# diff_probe.net
KiCad netlist of a schematic drawn in EAGLE
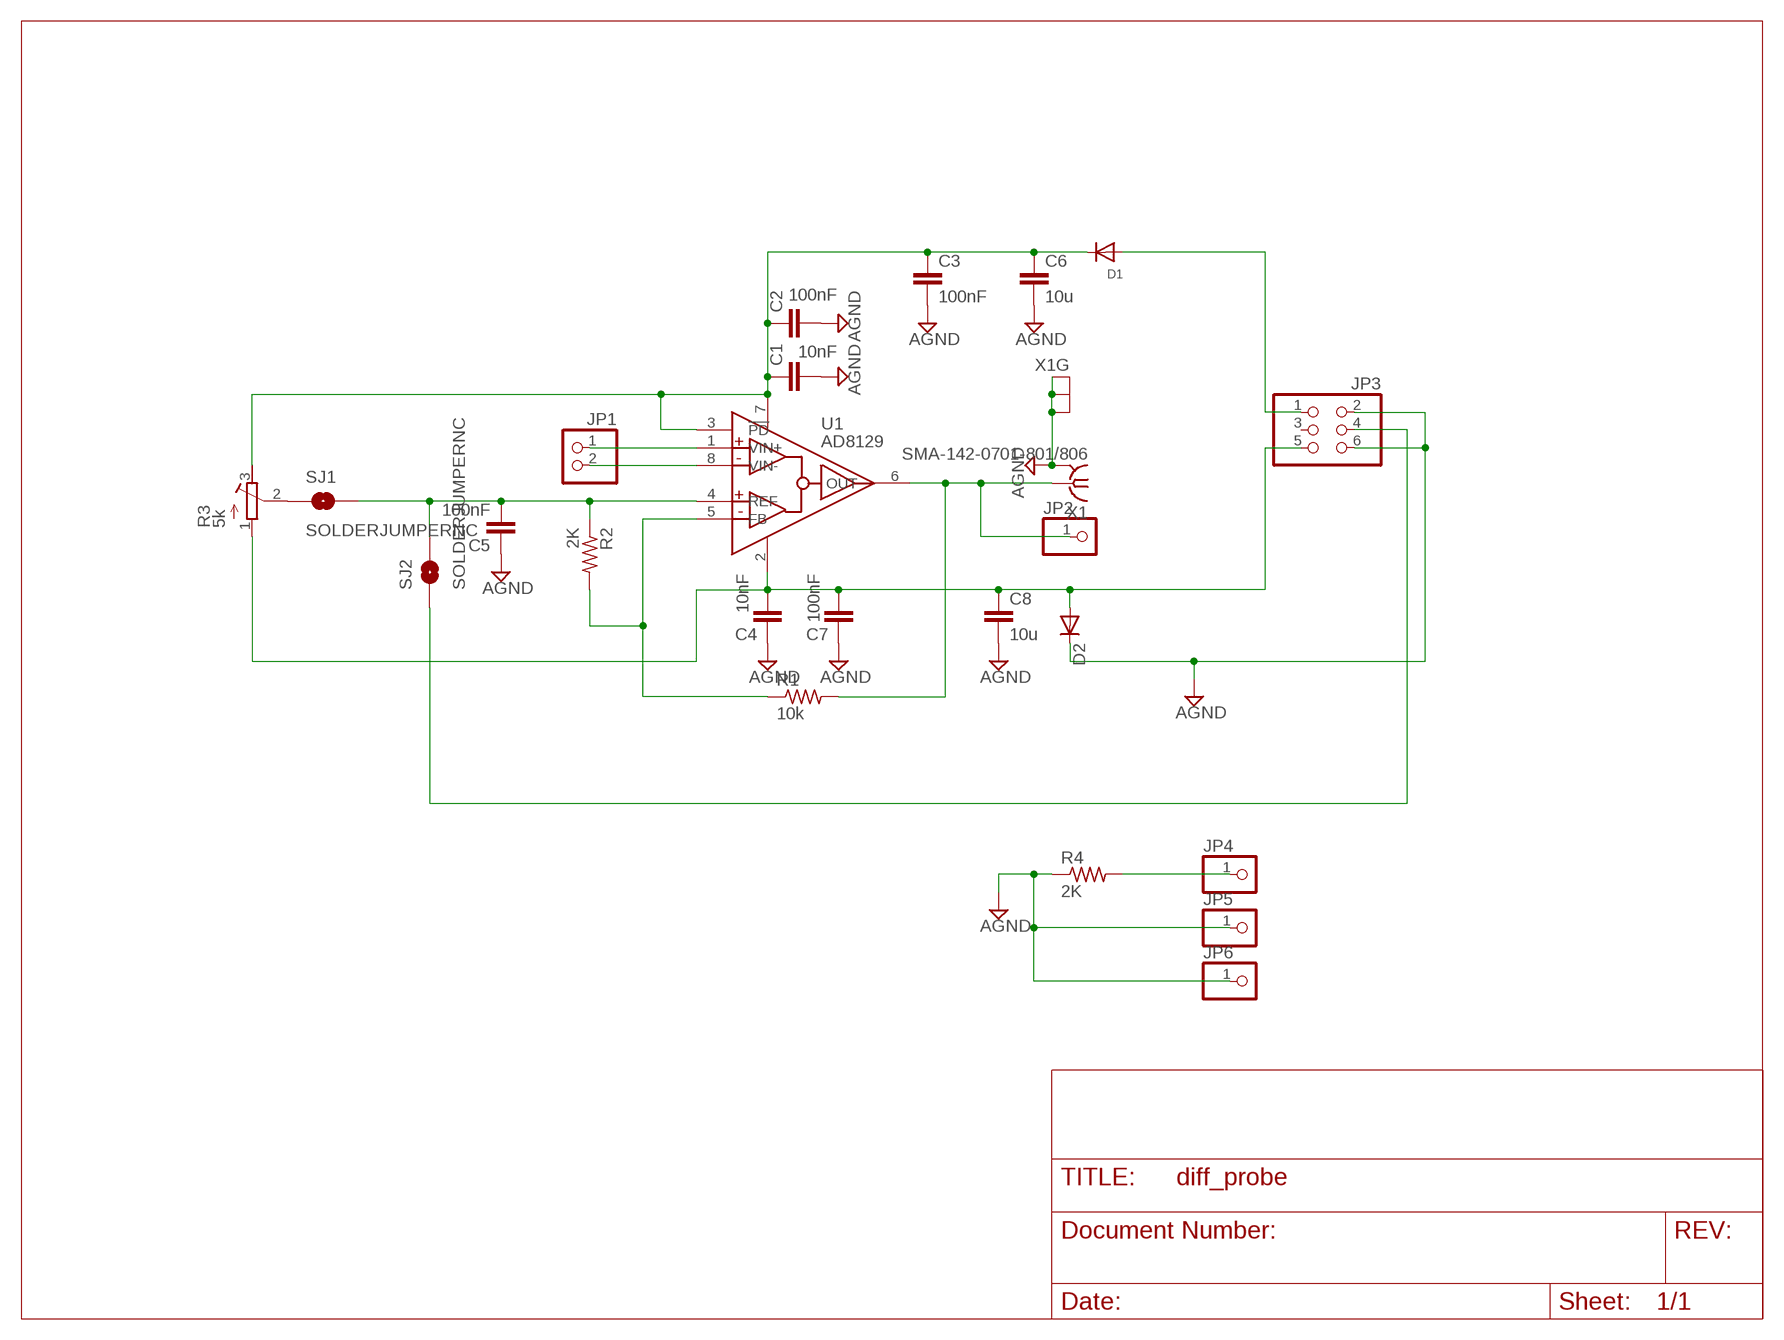
[diagram p0: schematic, sheet 1]

(export (version "E")
  (design (tool "Eeschema 10.0.6"))
  (components
    (comp (ref "C1")
      (value "10nF")
      (footprint "eagle-import:C0603")
      (libsource (lib "eagle-import") (part "C-EUC0603"))
    )
    (comp (ref "C2")
      (value "100nF")
      (footprint "eagle-import:C0603")
      (libsource (lib "eagle-import") (part "C-EUC0603"))
    )
    (comp (ref "C3")
      (value "100nF")
      (footprint "eagle-import:C0603")
      (libsource (lib "eagle-import") (part "C-EUC0603"))
    )
    (comp (ref "C4")
      (value "10nF")
      (footprint "eagle-import:C0603")
      (libsource (lib "eagle-import") (part "C-EUC0603"))
    )
    (comp (ref "C5")
      (value "100nF")
      (footprint "eagle-import:C0603")
      (libsource (lib "eagle-import") (part "C-EUC0603"))
    )
    (comp (ref "C6")
      (value "10u")
      (footprint "eagle-import:C0805")
      (libsource (lib "eagle-import") (part "C-EUC0805"))
    )
    (comp (ref "C7")
      (value "100nF")
      (footprint "eagle-import:C0603")
      (libsource (lib "eagle-import") (part "C-EUC0603"))
    )
    (comp (ref "C8")
      (value "10u")
      (footprint "eagle-import:C0805")
      (libsource (lib "eagle-import") (part "C-EUC0805"))
    )
    (comp (ref "D1")
      (value "DIODESOD-123")
      (footprint "eagle-import:SOD-123")
      (libsource (lib "eagle-import") (part "DIODESOD-123"))
    )
    (comp (ref "D2")
      (value "DIODE-DO-214AC")
      (footprint "eagle-import:DO-214AC")
      (libsource (lib "eagle-import") (part "DIODE-DO-214AC"))
    )
    (comp (ref "JP1")
      (value "PINHD-1X2/90")
      (footprint "eagle-import:1X02_90")
      (libsource (lib "eagle-import") (part "PINHD-1X2/90"))
    )
    (comp (ref "JP2")
      (value "PINHD-1X1")
      (footprint "eagle-import:1X01")
      (libsource (lib "eagle-import") (part "PINHD-1X1"))
    )
    (comp (ref "JP3")
      (value "PINHD-2X3EDGE")
      (footprint "eagle-import:6PAD_ISP")
      (libsource (lib "eagle-import") (part "PINHD-2X3EDGE"))
    )
    (comp (ref "JP4")
      (value "PINHD-1X1")
      (footprint "eagle-import:1X01")
      (libsource (lib "eagle-import") (part "PINHD-1X1"))
    )
    (comp (ref "JP5")
      (value "PINHD-1X1")
      (footprint "eagle-import:1X01")
      (libsource (lib "eagle-import") (part "PINHD-1X1"))
    )
    (comp (ref "JP6")
      (value "PINHD-1X1")
      (footprint "eagle-import:1X01")
      (libsource (lib "eagle-import") (part "PINHD-1X1"))
    )
    (comp (ref "R1")
      (value "10k")
      (footprint "eagle-import:R0603")
      (libsource (lib "eagle-import") (part "R-US_R0603"))
    )
    (comp (ref "R2")
      (value "2K")
      (footprint "eagle-import:R0603")
      (libsource (lib "eagle-import") (part "R-US_R0603"))
    )
    (comp (ref "R3")
      (value "5k")
      (footprint "eagle-import:RTRIM3224J")
      (libsource (lib "eagle-import") (part "R-TRIMM3224J"))
    )
    (comp (ref "R4")
      (value "2K")
      (footprint "eagle-import:R0603")
      (libsource (lib "eagle-import") (part "R-US_R0603"))
    )
    (comp (ref "SJ1")
      (value "SOLDERJUMPERNC")
      (footprint "eagle-import:SJ_2S")
      (libsource (lib "eagle-import") (part "SOLDERJUMPERNC"))
    )
    (comp (ref "SJ2")
      (value "SOLDERJUMPERNC")
      (footprint "eagle-import:SJ_2S")
      (libsource (lib "eagle-import") (part "SOLDERJUMPERNC"))
    )
    (comp (ref "U1")
      (value "AD8129")
      (footprint "eagle-import:SO08")
      (libsource (lib "eagle-import") (part "AD8129"))
    )
    (comp (ref "X1")
      (value "SMA-142-0701-801/806")
      (footprint "eagle-import:J502-ND-142-0701-801_806")
      (fields (field (name "MF") "JOHNSON COMPONENTS") (field (name "MPN") "142-0701-801"))
      (libsource (lib "eagle-import") (part "SMA-142-0701-801/806"))
    )
  )
  (nets
    (net (code "1") (name "AGND") (class "Default")
      (node (ref "C1") (pin "2") (pinfunction "2_2") (pintype "passive"))
      (node (ref "C2") (pin "2") (pinfunction "2_2") (pintype "passive"))
      (node (ref "C3") (pin "2") (pinfunction "2_2") (pintype "passive"))
      (node (ref "C4") (pin "1") (pinfunction "1_1") (pintype "passive"))
      (node (ref "C5") (pin "1") (pinfunction "1_1") (pintype "passive"))
      (node (ref "C6") (pin "2") (pinfunction "2_2") (pintype "passive"))
      (node (ref "C7") (pin "1") (pinfunction "1_1") (pintype "passive"))
      (node (ref "C8") (pin "2") (pinfunction "2_2") (pintype "passive"))
      (node (ref "D2") (pin "C") (pinfunction "C_C") (pintype "passive"))
      (node (ref "JP3") (pin "2") (pinfunction "1_2") (pintype "passive"))
      (node (ref "JP3") (pin "6") (pinfunction "5_6") (pintype "passive"))
      (node (ref "JP5") (pin "1") (pinfunction "1_1") (pintype "passive"))
      (node (ref "JP6") (pin "1") (pinfunction "1_1") (pintype "passive"))
      (node (ref "R4") (pin "1") (pinfunction "1_1") (pintype "passive"))
      (node (ref "X1") (pin "G@1") (pinfunction "GND_G@1") (pintype "power_in"))
      (node (ref "X1") (pin "G@2") (pinfunction "GND_G@2") (pintype "power_in"))
      (node (ref "X1") (pin "G@3") (pinfunction "GND_G@3") (pintype "power_in"))
      (node (ref "X1") (pin "G@4") (pinfunction "GND_G@4") (pintype "power_in"))
    )
    (net (code "2") (name "Net-(JP3-2)") (class "Default")
      (node (ref "D1") (pin "A") (pinfunction "A_A") (pintype "passive"))
      (node (ref "JP3") (pin "1") (pinfunction "2_1") (pintype "passive"))
    )
    (net (code "3") (name "Net-(JP3-3)") (class "Default")
      (node (ref "JP3") (pin "4") (pinfunction "3_4") (pintype "passive"))
      (node (ref "SJ2") (pin "1") (pinfunction "1_1") (pintype "passive"))
    )
    (net (code "4") (name "Net-(JP3-6)") (class "Default")
      (node (ref "C4") (pin "2") (pinfunction "2_2") (pintype "passive"))
      (node (ref "C7") (pin "2") (pinfunction "2_2") (pintype "passive"))
      (node (ref "C8") (pin "1") (pinfunction "1_1") (pintype "passive"))
      (node (ref "D2") (pin "A") (pinfunction "A_A") (pintype "passive"))
      (node (ref "JP3") (pin "5") (pinfunction "6_5") (pintype "passive"))
      (node (ref "R3") (pin "1") (pinfunction "E_1") (pintype "passive"))
      (node (ref "U1") (pin "2") (pinfunction "VSS_2") (pintype "power_in"))
    )
    (net (code "5") (name "Net-(JP4-Pad1)") (class "Default")
      (node (ref "JP4") (pin "1") (pinfunction "1_1") (pintype "passive"))
      (node (ref "R4") (pin "2") (pinfunction "2_2") (pintype "passive"))
    )
    (net (code "6") (name "Net-(R3-A)") (class "Default")
      (node (ref "C1") (pin "1") (pinfunction "1_1") (pintype "passive"))
      (node (ref "C2") (pin "1") (pinfunction "1_1") (pintype "passive"))
      (node (ref "C3") (pin "1") (pinfunction "1_1") (pintype "passive"))
      (node (ref "C6") (pin "1") (pinfunction "1_1") (pintype "passive"))
      (node (ref "D1") (pin "C") (pinfunction "C_C") (pintype "passive"))
      (node (ref "R3") (pin "3") (pinfunction "A_3") (pintype "passive"))
      (node (ref "U1") (pin "3") (pinfunction "~{PD}_3") (pintype "bidirectional"))
      (node (ref "U1") (pin "7") (pinfunction "VCC_7") (pintype "power_in"))
    )
    (net (code "7") (name "Net-(R3-S)") (class "Default")
      (node (ref "R3") (pin "2") (pinfunction "S_2") (pintype "passive"))
      (node (ref "SJ1") (pin "1") (pinfunction "1_1") (pintype "passive"))
    )
    (net (code "8") (name "Net-(U1-FB)") (class "Default")
      (node (ref "R1") (pin "1") (pinfunction "1_1") (pintype "passive"))
      (node (ref "R2") (pin "2") (pinfunction "2_2") (pintype "passive"))
      (node (ref "U1") (pin "5") (pinfunction "FB_5") (pintype "bidirectional"))
    )
    (net (code "9") (name "Net-(U1-OUT)") (class "Default")
      (node (ref "JP2") (pin "1") (pinfunction "1_1") (pintype "passive"))
      (node (ref "R1") (pin "2") (pinfunction "2_2") (pintype "passive"))
      (node (ref "U1") (pin "6") (pinfunction "OUT_6") (pintype "bidirectional"))
      (node (ref "X1") (pin "1") (pinfunction "1_1") (pintype "passive"))
    )
    (net (code "10") (name "Net-(U1-REF)") (class "Default")
      (node (ref "C5") (pin "2") (pinfunction "2_2") (pintype "passive"))
      (node (ref "R2") (pin "1") (pinfunction "1_1") (pintype "passive"))
      (node (ref "SJ1") (pin "2") (pinfunction "2_2") (pintype "passive"))
      (node (ref "SJ2") (pin "2") (pinfunction "2_2") (pintype "passive"))
      (node (ref "U1") (pin "4") (pinfunction "REF_4") (pintype "bidirectional"))
    )
    (net (code "11") (name "Net-(U1-VIN+)") (class "Default")
      (node (ref "JP1") (pin "1") (pinfunction "1_1") (pintype "passive"))
      (node (ref "U1") (pin "1") (pinfunction "VIN+_1") (pintype "bidirectional"))
    )
    (net (code "12") (name "Net-(U1-VIN-)") (class "Default")
      (node (ref "JP1") (pin "2") (pinfunction "2_2") (pintype "passive"))
      (node (ref "U1") (pin "8") (pinfunction "VIN-_8") (pintype "bidirectional"))
    )
    (net (code "13") (name "unconnected-(JP3-4-Pad3)") (class "Default")
      (node (ref "JP3") (pin "3") (pinfunction "4_3") (pintype "passive"))
    )
  )
)
